# ftdi_breakout.net
KiCad netlist of a schematic drawn in EAGLE
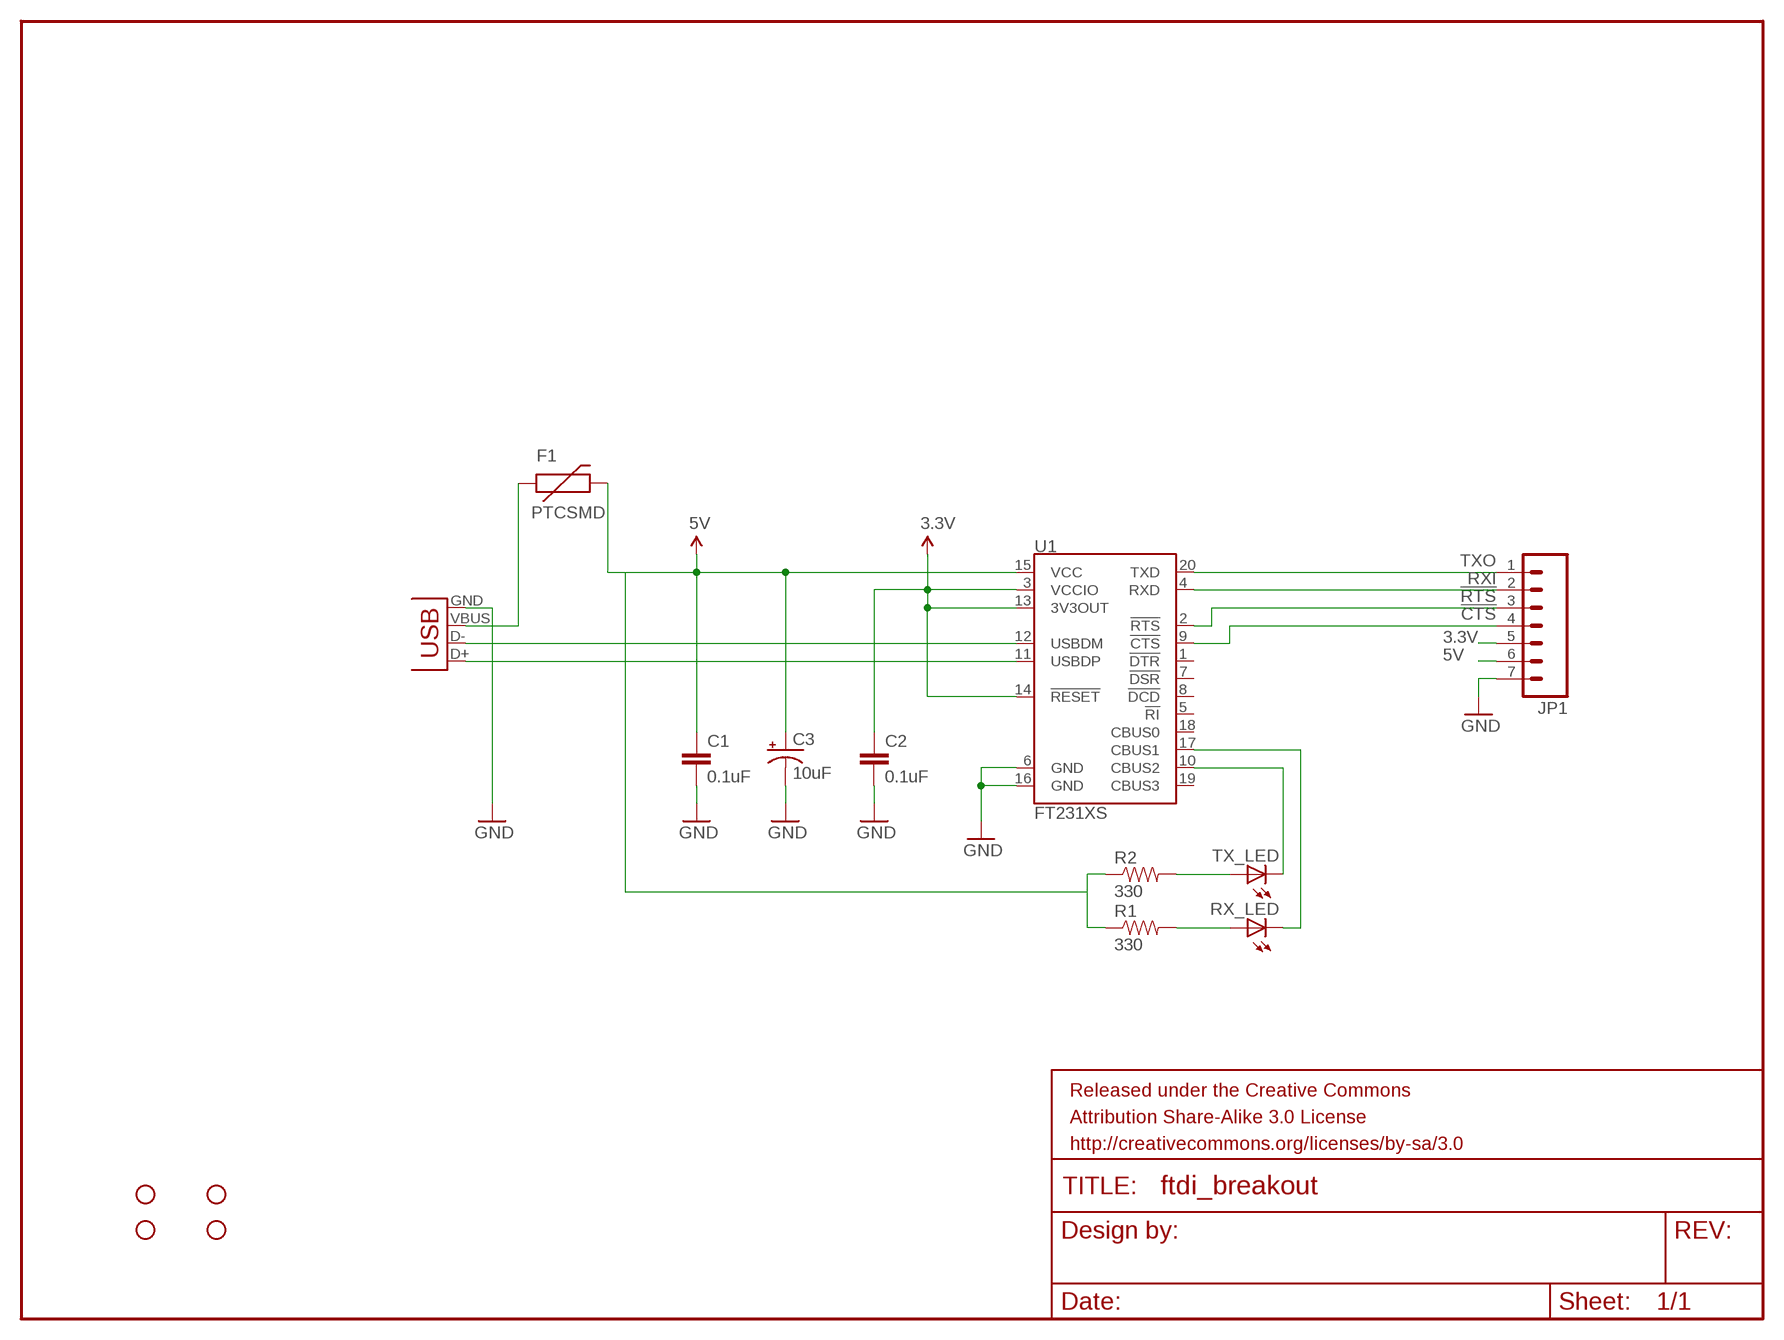
[diagram p0: schematic, sheet 1]

(export (version "E")
  (design (tool "Eeschema 10.0.6"))
  (components
    (comp (ref "C1")
      (value "0.1uF")
      (footprint "eagle-import:0603-CAP")
      (libsource (lib "eagle-import") (part "CAP0603-CAP"))
    )
    (comp (ref "C2")
      (value "0.1uF")
      (footprint "eagle-import:0603-CAP")
      (libsource (lib "eagle-import") (part "CAP0603-CAP"))
    )
    (comp (ref "C3")
      (value "10uF")
      (footprint "eagle-import:EIA3216")
      (libsource (lib "eagle-import") (part "CAP_POL1206"))
    )
    (comp (ref "F1")
      (value "PTCSMD")
      (footprint "eagle-import:PTC-1206")
      (libsource (lib "eagle-import") (part "PTCSMD"))
    )
    (comp (ref "FRAME1")
      (value "FRAME-LETTER")
      (footprint "eagle-import:CREATIVE_COMMONS")
      (libsource (lib "eagle-import") (part "FRAME-LETTER"))
    )
    (comp (ref "JP1")
      (value "M07")
      (footprint "eagle-import:1X07")
      (libsource (lib "eagle-import") (part "M07"))
    )
    (comp (ref "JP3")
      (value "USBSMD")
      (footprint "eagle-import:USB-MINIB")
      (libsource (lib "eagle-import") (part "USBSMD"))
    )
    (comp (ref "R1")
      (value "330")
      (footprint "eagle-import:0603-RES")
      (libsource (lib "eagle-import") (part "RESISTOR0603-RES"))
    )
    (comp (ref "R2")
      (value "330")
      (footprint "eagle-import:0603-RES")
      (libsource (lib "eagle-import") (part "RESISTOR0603-RES"))
    )
    (comp (ref "RX_LED")
      (value "LED0603")
      (footprint "eagle-import:LED-0603")
      (libsource (lib "eagle-import") (part "LED0603"))
    )
    (comp (ref "STANDOFF1")
      (value "STAND-OFF")
      (footprint "eagle-import:STAND-OFF")
      (libsource (lib "eagle-import") (part "STAND-OFF"))
    )
    (comp (ref "STANDOFF2")
      (value "STAND-OFF")
      (footprint "eagle-import:STAND-OFF")
      (libsource (lib "eagle-import") (part "STAND-OFF"))
    )
    (comp (ref "STANDOFF3")
      (value "STAND-OFF")
      (footprint "eagle-import:STAND-OFF")
      (libsource (lib "eagle-import") (part "STAND-OFF"))
    )
    (comp (ref "STANDOFF4")
      (value "STAND-OFF")
      (footprint "eagle-import:STAND-OFF")
      (libsource (lib "eagle-import") (part "STAND-OFF"))
    )
    (comp (ref "TX_LED")
      (value "LED0603")
      (footprint "eagle-import:LED-0603")
      (libsource (lib "eagle-import") (part "LED0603"))
    )
    (comp (ref "U1")
      (value "FT231XS")
      (footprint "eagle-import:SSOP20_L")
      (libsource (lib "eagle-import") (part "FT231XS"))
    )
  )
  (nets
    (net (code "1") (name "/RXI") (class "Default")
      (node (ref "JP1") (pin "2") (pinfunction "2_2") (pintype "passive"))
      (node (ref "U1") (pin "4") (pinfunction "RXD_4") (pintype "bidirectional"))
    )
    (net (code "2") (name "/TXO") (class "Default")
      (node (ref "JP1") (pin "1") (pinfunction "1_1") (pintype "passive"))
      (node (ref "U1") (pin "20") (pinfunction "TXD_20") (pintype "bidirectional"))
    )
    (net (code "3") (name "/~{CTS}") (class "Default")
      (node (ref "JP1") (pin "4") (pinfunction "4_4") (pintype "passive"))
      (node (ref "U1") (pin "9") (pinfunction "~{CTS}_9") (pintype "bidirectional"))
    )
    (net (code "4") (name "/~{RTS}") (class "Default")
      (node (ref "JP1") (pin "3") (pinfunction "3_3") (pintype "passive"))
      (node (ref "U1") (pin "2") (pinfunction "~{RTS}_2") (pintype "bidirectional"))
    )
    (net (code "5") (name "3.3V") (class "Default")
      (node (ref "C2") (pin "1") (pinfunction "1_1") (pintype "passive"))
      (node (ref "JP1") (pin "5") (pinfunction "5_5") (pintype "passive"))
      (node (ref "U1") (pin "13") (pinfunction "3V3OUT_13") (pintype "bidirectional"))
      (node (ref "U1") (pin "14") (pinfunction "~{RESET}_14") (pintype "bidirectional"))
      (node (ref "U1") (pin "3") (pinfunction "VCCIO_3") (pintype "bidirectional"))
    )
    (net (code "6") (name "5V") (class "Default")
      (node (ref "C1") (pin "1") (pinfunction "1_1") (pintype "passive"))
      (node (ref "C3") (pin "A") (pinfunction "+_A") (pintype "passive"))
      (node (ref "F1") (pin "2") (pinfunction "2_2") (pintype "bidirectional"))
      (node (ref "JP1") (pin "6") (pinfunction "6_6") (pintype "passive"))
      (node (ref "R1") (pin "1") (pinfunction "1_1") (pintype "passive"))
      (node (ref "R2") (pin "1") (pinfunction "1_1") (pintype "passive"))
      (node (ref "U1") (pin "15") (pinfunction "VCC_15") (pintype "bidirectional"))
    )
    (net (code "7") (name "GND") (class "Default")
      (node (ref "C1") (pin "2") (pinfunction "2_2") (pintype "passive"))
      (node (ref "C2") (pin "2") (pinfunction "2_2") (pintype "passive"))
      (node (ref "C3") (pin "C") (pinfunction "-_C") (pintype "passive"))
      (node (ref "JP1") (pin "7") (pinfunction "7_7") (pintype "passive"))
      (node (ref "JP3") (pin "GND") (pinfunction "GND_GND") (pintype "bidirectional"))
      (node (ref "U1") (pin "16") (pinfunction "GND_16") (pintype "bidirectional"))
      (node (ref "U1") (pin "6") (pinfunction "GND_6") (pintype "bidirectional"))
    )
    (net (code "8") (name "Net-(F1-Pad1)") (class "Default")
      (node (ref "F1") (pin "1") (pinfunction "1_1") (pintype "bidirectional"))
      (node (ref "JP3") (pin "VBUS") (pinfunction "VBUS_VBUS") (pintype "bidirectional"))
    )
    (net (code "9") (name "Net-(R1-Pad2)") (class "Default")
      (node (ref "R1") (pin "2") (pinfunction "2_2") (pintype "passive"))
      (node (ref "RX_LED") (pin "A") (pinfunction "A_A") (pintype "passive"))
    )
    (net (code "10") (name "Net-(R2-Pad2)") (class "Default")
      (node (ref "R2") (pin "2") (pinfunction "2_2") (pintype "passive"))
      (node (ref "TX_LED") (pin "A") (pinfunction "A_A") (pintype "passive"))
    )
    (net (code "11") (name "Net-(U1-CBUS1)") (class "Default")
      (node (ref "RX_LED") (pin "C") (pinfunction "C_C") (pintype "passive"))
      (node (ref "U1") (pin "17") (pinfunction "CBUS1_17") (pintype "bidirectional"))
    )
    (net (code "12") (name "Net-(U1-CBUS2)") (class "Default")
      (node (ref "TX_LED") (pin "C") (pinfunction "C_C") (pintype "passive"))
      (node (ref "U1") (pin "10") (pinfunction "CBUS2_10") (pintype "bidirectional"))
    )
    (net (code "13") (name "Net-(U1-USBDM)") (class "Default")
      (node (ref "JP3") (pin "D-") (pinfunction "D-_D-") (pintype "bidirectional"))
      (node (ref "U1") (pin "12") (pinfunction "USBDM_12") (pintype "bidirectional"))
    )
    (net (code "14") (name "Net-(U1-USBDP)") (class "Default")
      (node (ref "JP3") (pin "D+") (pinfunction "D+_D+") (pintype "bidirectional"))
      (node (ref "U1") (pin "11") (pinfunction "USBDP_11") (pintype "bidirectional"))
    )
    (net (code "15") (name "unconnected-(U1-CBUS0-Pad18)") (class "Default")
      (node (ref "U1") (pin "18") (pinfunction "CBUS0_18") (pintype "bidirectional"))
    )
    (net (code "16") (name "unconnected-(U1-CBUS3-Pad19)") (class "Default")
      (node (ref "U1") (pin "19") (pinfunction "CBUS3_19") (pintype "bidirectional"))
    )
    (net (code "17") (name "unconnected-(U1-~{DCD}-Pad8)") (class "Default")
      (node (ref "U1") (pin "8") (pinfunction "~{DCD}_8") (pintype "bidirectional"))
    )
    (net (code "18") (name "unconnected-(U1-~{DSR}-Pad7)") (class "Default")
      (node (ref "U1") (pin "7") (pinfunction "~{DSR}_7") (pintype "bidirectional"))
    )
    (net (code "19") (name "unconnected-(U1-~{DTR}-Pad1)") (class "Default")
      (node (ref "U1") (pin "1") (pinfunction "~{DTR}_1") (pintype "bidirectional"))
    )
    (net (code "20") (name "unconnected-(U1-~{RI}-Pad5)") (class "Default")
      (node (ref "U1") (pin "5") (pinfunction "~{RI}_5") (pintype "bidirectional"))
    )
  )
)
